# 02_Hum_Temp_Sensor.net
KiCad netlist of a schematic drawn in Altium Designer
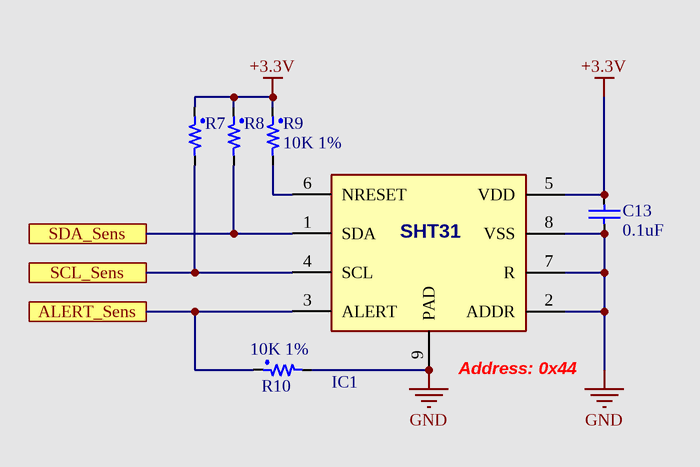
[diagram p0: 02_Hum_Temp_Sensor.SchDoc]

(export (version "E")
  (design (tool "Eeschema 10.0.6"))
  (components
    (comp (ref "C13")
      (value "0.1uF")
      (footprint "Capacitor:C0603 (1608 metric)")
      (description "Multilayer Ceramic Capacitors MLCC - SMD/SMT 0.1uF 50V X7R +/-10% 0603")
      (fields (field (name "MFR PART NUMBER") "CC0603KRX7R9BB104") (field (name "MFR") "Yageo"))
      (libsource (lib "CeramicCapacitor") (part "CC0603KRX7R9BB104"))
    )
    (comp (ref "IC1")
      (value "SHT31A-DIS-B10kS")
      (footprint "SHT31")
      (description "Board Mount Humidity Sensors RH/ T Sensor, Automotive certified")
      (fields (field (name "MFR") "Sensirion") (field (name "ARROW PART NUMBER") "SHT31A-DIS-B10KS"))
      (libsource (lib "Sensor") (part "SHT31A-DIS-B10kS"))
    )
    (comp (ref "R7")
      (value "10K 1%")
      (footprint "Resistor:R0603 (1608 Metric)")
      (description "Thick Film Resistors - SMD 10K OHM 1% Case 0603")
      (fields (field (name "MFR PART NUMBER") "RC0603FR-0710KL") (field (name "MFR") "Yageo"))
      (libsource (lib "ChipResistor") (part "RC0603FR-0710KL"))
    )
    (comp (ref "R8")
      (value "10K 1%")
      (footprint "Resistor:R0603 (1608 Metric)")
      (description "Thick Film Resistors - SMD 10K OHM 1% Case 0603")
      (fields (field (name "MFR PART NUMBER") "RC0603FR-0710KL") (field (name "MFR") "Yageo"))
      (libsource (lib "ChipResistor") (part "RC0603FR-0710KL"))
    )
    (comp (ref "R9")
      (value "10K 1%")
      (footprint "Resistor:R0603 (1608 Metric)")
      (description "Thick Film Resistors - SMD 10K OHM 1% Case 0603")
      (fields (field (name "MFR PART NUMBER") "RC0603FR-0710KL") (field (name "MFR") "Yageo"))
      (libsource (lib "ChipResistor") (part "RC0603FR-0710KL"))
    )
    (comp (ref "R10")
      (value "10K 1%")
      (footprint "Resistor:R0603 (1608 Metric)")
      (description "Thick Film Resistors - SMD 10K OHM 1% Case 0603")
      (fields (field (name "MFR PART NUMBER") "RC0603FR-0710KL") (field (name "MFR") "Yageo"))
      (libsource (lib "ChipResistor") (part "RC0603FR-0710KL"))
    )
  )
  (nets
    (net (code "1") (name "+3.3V") (class "Default")
      (node (ref "C13") (pin "2") (pinfunction "2_2") (pintype "passive"))
      (node (ref "IC1") (pin "5") (pinfunction "VDD_5") (pintype "passive"))
      (node (ref "R7") (pin "1") (pinfunction "1_1") (pintype "passive"))
      (node (ref "R8") (pin "1") (pinfunction "1_1") (pintype "passive"))
      (node (ref "R9") (pin "1") (pinfunction "1_1") (pintype "passive"))
    )
    (net (code "2") (name "/ALERT_Sens") (class "Default")
      (node (ref "IC1") (pin "3") (pinfunction "ALERT_3") (pintype "passive"))
      (node (ref "R10") (pin "1") (pinfunction "1_1") (pintype "passive"))
    )
    (net (code "3") (name "/SCL_Sens") (class "Default")
      (node (ref "IC1") (pin "4") (pinfunction "SCL_4") (pintype "passive"))
      (node (ref "R7") (pin "2") (pinfunction "2_2") (pintype "passive"))
    )
    (net (code "4") (name "/SDA_Sens") (class "Default")
      (node (ref "IC1") (pin "1") (pinfunction "SDA_1") (pintype "passive"))
      (node (ref "R8") (pin "2") (pinfunction "2_2") (pintype "passive"))
    )
    (net (code "5") (name "GND") (class "Default")
      (node (ref "C13") (pin "1") (pinfunction "1_1") (pintype "passive"))
      (node (ref "IC1") (pin "2") (pinfunction "ADDR_2") (pintype "passive"))
      (node (ref "IC1") (pin "7") (pinfunction "R_7") (pintype "passive"))
      (node (ref "IC1") (pin "8") (pinfunction "VSS_8") (pintype "passive"))
      (node (ref "IC1") (pin "9") (pinfunction "PAD_9") (pintype "passive"))
      (node (ref "R10") (pin "2") (pinfunction "2_2") (pintype "passive"))
    )
    (net (code "6") (name "Net-(IC1-NRESET)") (class "Default")
      (node (ref "IC1") (pin "6") (pinfunction "NRESET_6") (pintype "passive"))
      (node (ref "R9") (pin "2") (pinfunction "2_2") (pintype "passive"))
    )
  )
)
